# RPI_Supply.net
KiCad netlist of a schematic drawn in Altium Designer
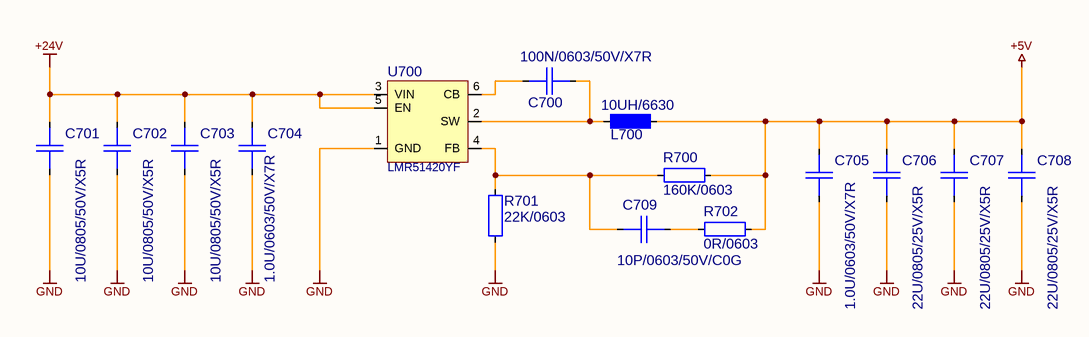
[diagram p0: RPI_Supply.SchDoc]

(export (version "E")
  (design (tool "Eeschema 10.0.6"))
  (components
    (comp (ref "C700")
      (value "100N/0603/50V/X7R")
      (footprint "CAP0603_X7R")
      (description "CAP SM 0603 100nF 50V X7R")
      (fields (field (name "MANUFACTURER") "GENERIC"))
      (libsource (lib "daniw_altium_lib") (part "C"))
    )
    (comp (ref "C701")
      (value "10U/0805/50V/X5R")
      (footprint "CAP0805_X7R")
      (description "CAP SM 0805 10uF 50V X5R")
      (fields (field (name "MANUFACTURER") "GENERIC"))
      (libsource (lib "daniw_altium_lib") (part "C"))
    )
    (comp (ref "C702")
      (value "10U/0805/50V/X5R")
      (footprint "CAP0805_X7R")
      (description "CAP SM 0805 10uF 50V X5R")
      (fields (field (name "MANUFACTURER") "GENERIC"))
      (libsource (lib "daniw_altium_lib") (part "C"))
    )
    (comp (ref "C703")
      (value "10U/0805/50V/X5R")
      (footprint "CAP0805_X7R")
      (description "CAP SM 0805 10uF 50V X5R")
      (fields (field (name "MANUFACTURER") "GENERIC"))
      (libsource (lib "daniw_altium_lib") (part "C"))
    )
    (comp (ref "C704")
      (value "1.0U/0603/50V/X7R")
      (footprint "CAP0603_X7R")
      (description "CAP SM 0603 1.0uF 50V X7R")
      (fields (field (name "MANUFACTURER") "GENERIC"))
      (libsource (lib "daniw_altium_lib") (part "C"))
    )
    (comp (ref "C705")
      (value "1.0U/0603/50V/X7R")
      (footprint "CAP0603_X7R")
      (description "CAP SM 0603 1.0uF 50V X7R")
      (fields (field (name "MANUFACTURER") "GENERIC"))
      (libsource (lib "daniw_altium_lib") (part "C"))
    )
    (comp (ref "C706")
      (value "22U/0805/25V/X5R")
      (footprint "CAP0805_X7R")
      (description "CAP SM 0805 22uF 25V X5R")
      (fields (field (name "MANUFACTURER") "GENERIC"))
      (libsource (lib "daniw_altium_lib") (part "C"))
    )
    (comp (ref "C707")
      (value "22U/0805/25V/X5R")
      (footprint "CAP0805_X7R")
      (description "CAP SM 0805 22uF 25V X5R")
      (fields (field (name "MANUFACTURER") "GENERIC"))
      (libsource (lib "daniw_altium_lib") (part "C"))
    )
    (comp (ref "C708")
      (value "22U/0805/25V/X5R")
      (footprint "CAP0805_X7R")
      (description "CAP SM 0805 22uF 25V X5R")
      (fields (field (name "MANUFACTURER") "GENERIC"))
      (libsource (lib "daniw_altium_lib") (part "C"))
    )
    (comp (ref "C709")
      (value "10P/0603/50V/C0G")
      (footprint "CAP0603_C0G")
      (description "CAP SM 0603 10pF 50V C0G")
      (fields (field (name "MANUFACTURER") "GENERIC"))
      (libsource (lib "daniw_altium_lib") (part "C"))
    )
    (comp (ref "L700")
      (value "10UH/6630")
      (footprint "INDM660730X30")
      (description "FIXED IND 10UH 4A 68 MOHM SMD")
      (fields (field (name "MANUFACTURER") "GENERIC"))
      (libsource (lib "daniw_altium_lib") (part "L"))
    )
    (comp (ref "R700")
      (value "160K/0603")
      (footprint "R0603-0.40-WW")
      (description "RES SM 0603 160K")
      (fields (field (name "MANUFACTURER") "GENERIC"))
      (libsource (lib "daniw_altium_lib") (part "R"))
    )
    (comp (ref "R701")
      (value "22K/0603")
      (footprint "R0603-0.40-WW")
      (description "RES SM 0603 22K")
      (fields (field (name "MANUFACTURER") "GENERIC"))
      (libsource (lib "daniw_altium_lib") (part "R"))
    )
    (comp (ref "R702")
      (value "0R/0603")
      (footprint "R0603-0.40-WW")
      (description "RES SM 0603 0R")
      (fields (field (name "MANUFACTURER") "GENERIC"))
      (libsource (lib "daniw_altium_lib") (part "R"))
    )
    (comp (ref "U700")
      (value "LMR51420YF")
      (footprint "SOT2395P280X125-6-NW")
      (description "SIMPLE SWITCHER® power converter 4.5-V to 36-V, 2-A, synchronous buck with 40-µA IQ")
      (fields (field (name "MANUFACTURER") "Texas Instruments"))
      (libsource (lib "daniw_altium_lib") (part "LMR51420"))
    )
  )
  (nets
    (net (code "1") (name "+5V") (class "Default")
      (node (ref "C705") (pin "1") (pinfunction "1_1") (pintype "passive"))
      (node (ref "C706") (pin "1") (pinfunction "1_1") (pintype "passive"))
      (node (ref "C707") (pin "1") (pinfunction "1_1") (pintype "passive"))
      (node (ref "C708") (pin "1") (pinfunction "1_1") (pintype "passive"))
      (node (ref "L700") (pin "2") (pinfunction "2_2") (pintype "passive"))
      (node (ref "R700") (pin "1") (pinfunction "1_1") (pintype "passive"))
      (node (ref "R702") (pin "2") (pinfunction "2_2") (pintype "passive"))
    )
    (net (code "2") (name "+24V") (class "Default")
      (node (ref "C701") (pin "1") (pinfunction "1_1") (pintype "passive"))
      (node (ref "C702") (pin "1") (pinfunction "1_1") (pintype "passive"))
      (node (ref "C703") (pin "1") (pinfunction "1_1") (pintype "passive"))
      (node (ref "C704") (pin "1") (pinfunction "1_1") (pintype "passive"))
      (node (ref "U700") (pin "3") (pinfunction "VIN_3") (pintype "passive"))
      (node (ref "U700") (pin "5") (pinfunction "EN_5") (pintype "passive"))
    )
    (net (code "3") (name "GND") (class "Default")
      (node (ref "C701") (pin "2") (pinfunction "2_2") (pintype "passive"))
      (node (ref "C702") (pin "2") (pinfunction "2_2") (pintype "passive"))
      (node (ref "C703") (pin "2") (pinfunction "2_2") (pintype "passive"))
      (node (ref "C704") (pin "2") (pinfunction "2_2") (pintype "passive"))
      (node (ref "C705") (pin "2") (pinfunction "2_2") (pintype "passive"))
      (node (ref "C706") (pin "2") (pinfunction "2_2") (pintype "passive"))
      (node (ref "C707") (pin "2") (pinfunction "2_2") (pintype "passive"))
      (node (ref "C708") (pin "2") (pinfunction "2_2") (pintype "passive"))
      (node (ref "R701") (pin "1") (pinfunction "1_1") (pintype "passive"))
      (node (ref "U700") (pin "1") (pinfunction "GND_1") (pintype "passive"))
    )
    (net (code "4") (name "Net-(C709-Pad2)") (class "Default")
      (node (ref "C709") (pin "2") (pinfunction "2_2") (pintype "passive"))
      (node (ref "R702") (pin "1") (pinfunction "1_1") (pintype "passive"))
    )
    (net (code "5") (name "Net-(U700-CB)") (class "Default")
      (node (ref "C700") (pin "1") (pinfunction "1_1") (pintype "passive"))
      (node (ref "U700") (pin "6") (pinfunction "CB_6") (pintype "passive"))
    )
    (net (code "6") (name "Net-(U700-FB)") (class "Default")
      (node (ref "C709") (pin "1") (pinfunction "1_1") (pintype "passive"))
      (node (ref "R700") (pin "2") (pinfunction "2_2") (pintype "passive"))
      (node (ref "R701") (pin "2") (pinfunction "2_2") (pintype "passive"))
      (node (ref "U700") (pin "4") (pinfunction "FB_4") (pintype "passive"))
    )
    (net (code "7") (name "Net-(U700-SW)") (class "Default")
      (node (ref "C700") (pin "2") (pinfunction "2_2") (pintype "passive"))
      (node (ref "L700") (pin "1") (pinfunction "1_1") (pintype "passive"))
      (node (ref "U700") (pin "2") (pinfunction "SW_2") (pintype "passive"))
    )
  )
)
